# powerboard.net
KiCad netlist of a schematic drawn in EAGLE
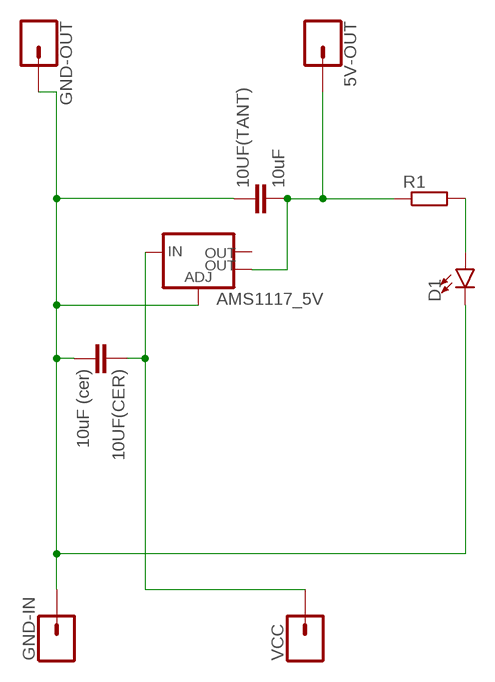
[diagram p0: schematic, sheet 1]

(export (version "E")
  (design (tool "Eeschema 10.0.6"))
  (components
    (comp (ref "5V-OUT")
      (value "CONN_01PTH_LONGPAD")
      (footprint "eagle-import:1X01_LONGPAD")
      (libsource (lib "eagle-import") (part "CONN_01PTH_LONGPAD"))
    )
    (comp (ref "10UF(CER)")
      (value "10uF (cer)")
      (footprint "eagle-import:1206")
      (libsource (lib "eagle-import") (part "10UF-1206-6.3V-20%"))
    )
    (comp (ref "10UF(TANT)")
      (value "10uF")
      (footprint "eagle-import:1206")
      (libsource (lib "eagle-import") (part "10UF-1206-6.3V-20%"))
    )
    (comp (ref "AMS1117_5V")
      (value "V_REG_LM1117SOT223")
      (footprint "eagle-import:SOT223")
      (libsource (lib "eagle-import") (part "V_REG_LM1117SOT223"))
    )
    (comp (ref "D1")
      (value "LED0603")
      (footprint "eagle-import:LED-0603")
      (libsource (lib "eagle-import") (part "LED0603"))
    )
    (comp (ref "GND-IN")
      (value "CONN_01PTH_LONGPAD")
      (footprint "eagle-import:1X01_LONGPAD")
      (libsource (lib "eagle-import") (part "CONN_01PTH_LONGPAD"))
    )
    (comp (ref "GND-OUT")
      (value "CONN_01PTH_LONGPAD")
      (footprint "eagle-import:1X01_LONGPAD")
      (libsource (lib "eagle-import") (part "CONN_01PTH_LONGPAD"))
    )
    (comp (ref "R1")
      (value "R-EU_R0603")
      (footprint "eagle-import:R0603")
      (libsource (lib "eagle-import") (part "R-EU_R0603"))
    )
    (comp (ref "VCC")
      (value "CONN_01PTH_LONGPAD")
      (footprint "eagle-import:1X01_LONGPAD")
      (libsource (lib "eagle-import") (part "CONN_01PTH_LONGPAD"))
    )
  )
  (nets
    (net (code "1") (name "Net-(10UF(TANT)-Pad2)") (class "Default")
      (node (ref "10UF(TANT)") (pin "2") (pinfunction "2_2") (pintype "passive"))
      (node (ref "5V-OUT") (pin "1") (pinfunction "1_1") (pintype "passive"))
      (node (ref "AMS1117_5V") (pin "4") (pinfunction "OUT_4") (pintype "output"))
      (node (ref "R1") (pin "1") (pinfunction "1_1") (pintype "passive"))
    )
    (net (code "2") (name "Net-(AMS1117_5V-ADJ)") (class "Default")
      (node (ref "10UF(CER)") (pin "2") (pinfunction "2_2") (pintype "passive"))
      (node (ref "10UF(TANT)") (pin "1") (pinfunction "1_1") (pintype "passive"))
      (node (ref "AMS1117_5V") (pin "1") (pinfunction "ADJ_1") (pintype "input"))
      (node (ref "D1") (pin "C") (pinfunction "C_C") (pintype "passive"))
      (node (ref "GND-IN") (pin "1") (pinfunction "1_1") (pintype "passive"))
      (node (ref "GND-OUT") (pin "1") (pinfunction "1_1") (pintype "passive"))
    )
    (net (code "3") (name "Net-(AMS1117_5V-IN)") (class "Default")
      (node (ref "10UF(CER)") (pin "1") (pinfunction "1_1") (pintype "passive"))
      (node (ref "AMS1117_5V") (pin "3") (pinfunction "IN_3") (pintype "input"))
      (node (ref "VCC") (pin "1") (pinfunction "1_1") (pintype "passive"))
    )
    (net (code "4") (name "Net-(D1-PadA)") (class "Default")
      (node (ref "D1") (pin "A") (pinfunction "A_A") (pintype "passive"))
      (node (ref "R1") (pin "2") (pinfunction "2_2") (pintype "passive"))
    )
    (net (code "5") (name "unconnected-(AMS1117_5V-OUT-Pad2)") (class "Default")
      (node (ref "AMS1117_5V") (pin "2") (pinfunction "OUT_2") (pintype "output"))
    )
  )
)
